# rapidshark-display-shifter-mk-1_0.net
KiCad netlist of a schematic drawn in EAGLE
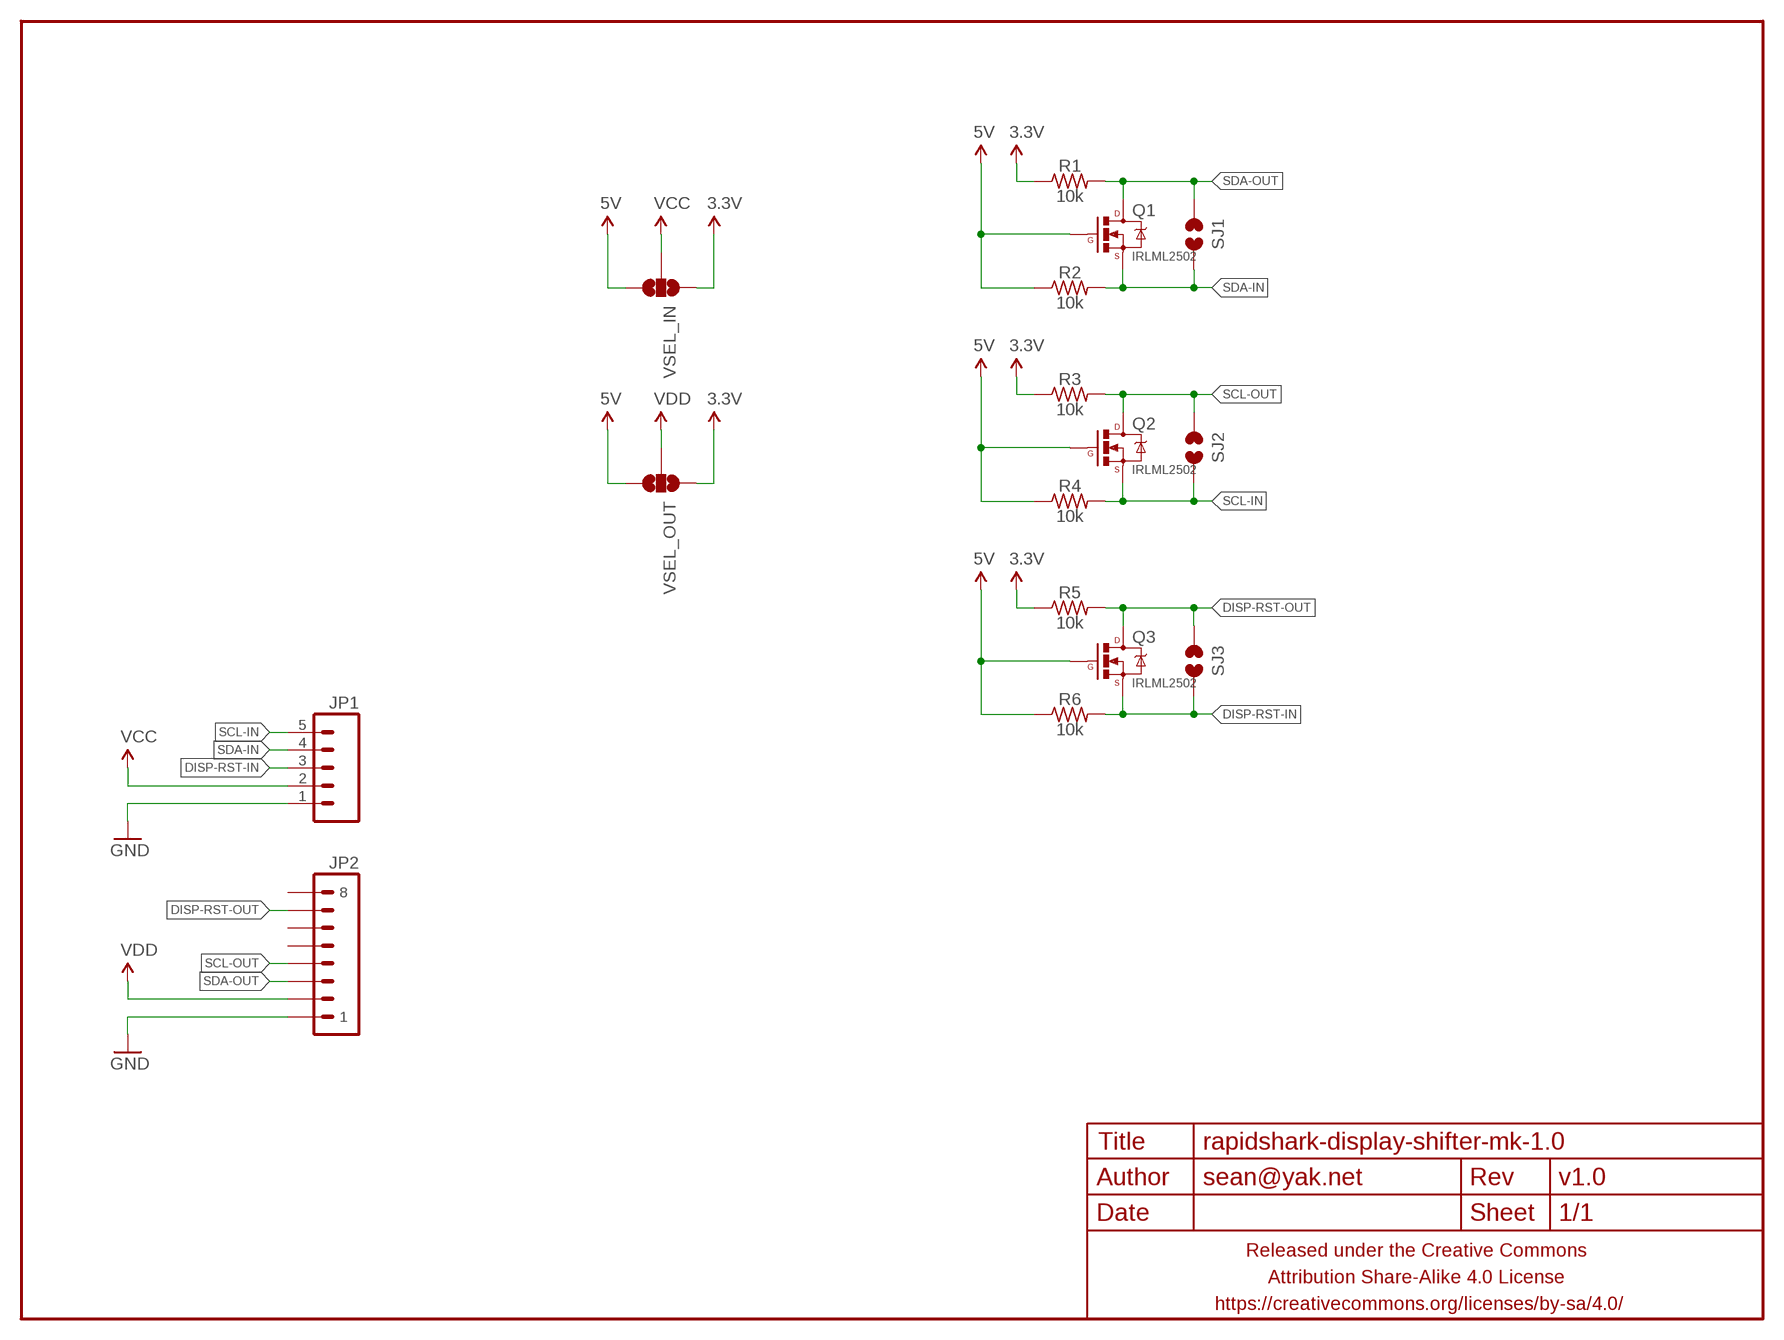
[diagram p0: schematic, sheet 1]

(export (version "E")
  (design (tool "Eeschema 10.0.6"))
  (components
    (comp (ref "FRAME1")
      (value "FRAME-LETTERNO_PACKAGE")
      (footprint "eagle-import:DUMMY")
      (fields (field (name "DESIGNER") "sean@yak.net") (field (name "VERSION") "v1.0"))
      (libsource (lib "eagle-import") (part "FRAME-LETTERNO_PACKAGE"))
    )
    (comp (ref "JP1")
      (value "M05JST-PH-VERT-PTH")
      (footprint "eagle-import:JST-5-PH-VERT-PTH")
      (libsource (lib "eagle-import") (part "M05JST-PH-VERT-PTH"))
    )
    (comp (ref "JP2")
      (value "M081X08")
      (footprint "eagle-import:1X08")
      (libsource (lib "eagle-import") (part "M081X08"))
    )
    (comp (ref "Q1")
      (value "IRLML2502")
      (footprint "eagle-import:SOT23")
      (libsource (lib "eagle-import") (part "MOSFET-NCHANNELIRLML2502"))
    )
    (comp (ref "Q2")
      (value "IRLML2502")
      (footprint "eagle-import:SOT23")
      (libsource (lib "eagle-import") (part "MOSFET-NCHANNELIRLML2502"))
    )
    (comp (ref "Q3")
      (value "IRLML2502")
      (footprint "eagle-import:SOT23")
      (libsource (lib "eagle-import") (part "MOSFET-NCHANNELIRLML2502"))
    )
    (comp (ref "R1")
      (value "10k")
      (footprint "eagle-import:R0805")
      (libsource (lib "eagle-import") (part "RESISTORR0805"))
    )
    (comp (ref "R2")
      (value "10k")
      (footprint "eagle-import:R0805")
      (libsource (lib "eagle-import") (part "RESISTORR0805"))
    )
    (comp (ref "R3")
      (value "10k")
      (footprint "eagle-import:R0805")
      (libsource (lib "eagle-import") (part "RESISTORR0805"))
    )
    (comp (ref "R4")
      (value "10k")
      (footprint "eagle-import:R0805")
      (libsource (lib "eagle-import") (part "RESISTORR0805"))
    )
    (comp (ref "R5")
      (value "10k")
      (footprint "eagle-import:R0805")
      (libsource (lib "eagle-import") (part "RESISTORR0805"))
    )
    (comp (ref "R6")
      (value "10k")
      (footprint "eagle-import:R0805")
      (libsource (lib "eagle-import") (part "RESISTORR0805"))
    )
    (comp (ref "SJ1")
      (value "JUMPER-PAD-2-NOYES_SILK")
      (footprint "eagle-import:PAD-JUMPER-2-NO_YES_SILK")
      (libsource (lib "eagle-import") (part "JUMPER-PAD-2-NOYES_SILK"))
    )
    (comp (ref "SJ2")
      (value "JUMPER-PAD-2-NOYES_SILK")
      (footprint "eagle-import:PAD-JUMPER-2-NO_YES_SILK")
      (libsource (lib "eagle-import") (part "JUMPER-PAD-2-NOYES_SILK"))
    )
    (comp (ref "SJ3")
      (value "JUMPER-PAD-2-NOYES_SILK")
      (footprint "eagle-import:PAD-JUMPER-2-NO_YES_SILK")
      (libsource (lib "eagle-import") (part "JUMPER-PAD-2-NOYES_SILK"))
    )
    (comp (ref "VSEL_IN")
      (value "JUMPER-PAD-3-NOFULL_BOX_SILK")
      (footprint "eagle-import:PAD-JUMPER-3-NO_YES_SILK_FULL_BOX")
      (libsource (lib "eagle-import") (part "JUMPER-PAD-3-NOFULL_BOX_SILK"))
    )
    (comp (ref "VSEL_OUT")
      (value "JUMPER-PAD-3-NOFULL_BOX_SILK")
      (footprint "eagle-import:PAD-JUMPER-3-NO_YES_SILK_FULL_BOX")
      (libsource (lib "eagle-import") (part "JUMPER-PAD-3-NOFULL_BOX_SILK"))
    )
  )
  (nets
    (net (code "1") (name "3.3V") (class "Default")
      (node (ref "R1") (pin "1") (pinfunction "1_1") (pintype "passive"))
      (node (ref "R3") (pin "1") (pinfunction "1_1") (pintype "passive"))
      (node (ref "R5") (pin "1") (pinfunction "1_1") (pintype "passive"))
      (node (ref "VSEL_IN") (pin "1") (pinfunction "1_1") (pintype "passive"))
      (node (ref "VSEL_OUT") (pin "1") (pinfunction "1_1") (pintype "passive"))
    )
    (net (code "2") (name "5V") (class "Default")
      (node (ref "Q1") (pin "1") (pinfunction "G_1") (pintype "passive"))
      (node (ref "Q2") (pin "1") (pinfunction "G_1") (pintype "passive"))
      (node (ref "Q3") (pin "1") (pinfunction "G_1") (pintype "passive"))
      (node (ref "R2") (pin "1") (pinfunction "1_1") (pintype "passive"))
      (node (ref "R4") (pin "1") (pinfunction "1_1") (pintype "passive"))
      (node (ref "R6") (pin "1") (pinfunction "1_1") (pintype "passive"))
      (node (ref "VSEL_IN") (pin "3") (pinfunction "3_3") (pintype "passive"))
      (node (ref "VSEL_OUT") (pin "3") (pinfunction "3_3") (pintype "passive"))
    )
    (net (code "3") (name "DISP-RST-IN") (class "Default")
      (node (ref "JP1") (pin "3") (pinfunction "3_3") (pintype "passive"))
      (node (ref "Q3") (pin "2") (pinfunction "S_2") (pintype "passive"))
      (node (ref "R6") (pin "2") (pinfunction "2_2") (pintype "passive"))
      (node (ref "SJ3") (pin "1") (pinfunction "1_1") (pintype "passive"))
    )
    (net (code "4") (name "DISP-RST-OUT") (class "Default")
      (node (ref "JP2") (pin "7") (pinfunction "7_7") (pintype "passive"))
      (node (ref "Q3") (pin "3") (pinfunction "D_3") (pintype "passive"))
      (node (ref "R5") (pin "2") (pinfunction "2_2") (pintype "passive"))
      (node (ref "SJ3") (pin "2") (pinfunction "2_2") (pintype "passive"))
    )
    (net (code "5") (name "GND") (class "Default")
      (node (ref "JP1") (pin "1") (pinfunction "1_1") (pintype "passive"))
      (node (ref "JP2") (pin "1") (pinfunction "1_1") (pintype "passive"))
    )
    (net (code "6") (name "SCL-IN") (class "Default")
      (node (ref "JP1") (pin "5") (pinfunction "5_5") (pintype "passive"))
      (node (ref "Q2") (pin "2") (pinfunction "S_2") (pintype "passive"))
      (node (ref "R4") (pin "2") (pinfunction "2_2") (pintype "passive"))
      (node (ref "SJ2") (pin "1") (pinfunction "1_1") (pintype "passive"))
    )
    (net (code "7") (name "SCL-OUT") (class "Default")
      (node (ref "JP2") (pin "4") (pinfunction "4_4") (pintype "passive"))
      (node (ref "Q2") (pin "3") (pinfunction "D_3") (pintype "passive"))
      (node (ref "R3") (pin "2") (pinfunction "2_2") (pintype "passive"))
      (node (ref "SJ2") (pin "2") (pinfunction "2_2") (pintype "passive"))
    )
    (net (code "8") (name "SDA-IN") (class "Default")
      (node (ref "JP1") (pin "4") (pinfunction "4_4") (pintype "passive"))
      (node (ref "Q1") (pin "2") (pinfunction "S_2") (pintype "passive"))
      (node (ref "R2") (pin "2") (pinfunction "2_2") (pintype "passive"))
      (node (ref "SJ1") (pin "1") (pinfunction "1_1") (pintype "passive"))
    )
    (net (code "9") (name "SDA-OUT") (class "Default")
      (node (ref "JP2") (pin "3") (pinfunction "3_3") (pintype "passive"))
      (node (ref "Q1") (pin "3") (pinfunction "D_3") (pintype "passive"))
      (node (ref "R1") (pin "2") (pinfunction "2_2") (pintype "passive"))
      (node (ref "SJ1") (pin "2") (pinfunction "2_2") (pintype "passive"))
    )
    (net (code "10") (name "VCC") (class "Default")
      (node (ref "JP1") (pin "2") (pinfunction "2_2") (pintype "passive"))
      (node (ref "VSEL_IN") (pin "2") (pinfunction "2_2") (pintype "passive"))
    )
    (net (code "11") (name "VDD") (class "Default")
      (node (ref "JP2") (pin "2") (pinfunction "2_2") (pintype "passive"))
      (node (ref "VSEL_OUT") (pin "2") (pinfunction "2_2") (pintype "passive"))
    )
    (net (code "12") (name "unconnected-(JP2-Pad5)") (class "Default")
      (node (ref "JP2") (pin "5") (pinfunction "5_5") (pintype "passive"))
    )
    (net (code "13") (name "unconnected-(JP2-Pad6)") (class "Default")
      (node (ref "JP2") (pin "6") (pinfunction "6_6") (pintype "passive"))
    )
    (net (code "14") (name "unconnected-(JP2-Pad8)") (class "Default")
      (node (ref "JP2") (pin "8") (pinfunction "8_8") (pintype "passive"))
    )
  )
)
